# ProPrj_OpenCartGBA_2024-06-17.net
KiCad netlist of a schematic drawn in EasyEDA Pro
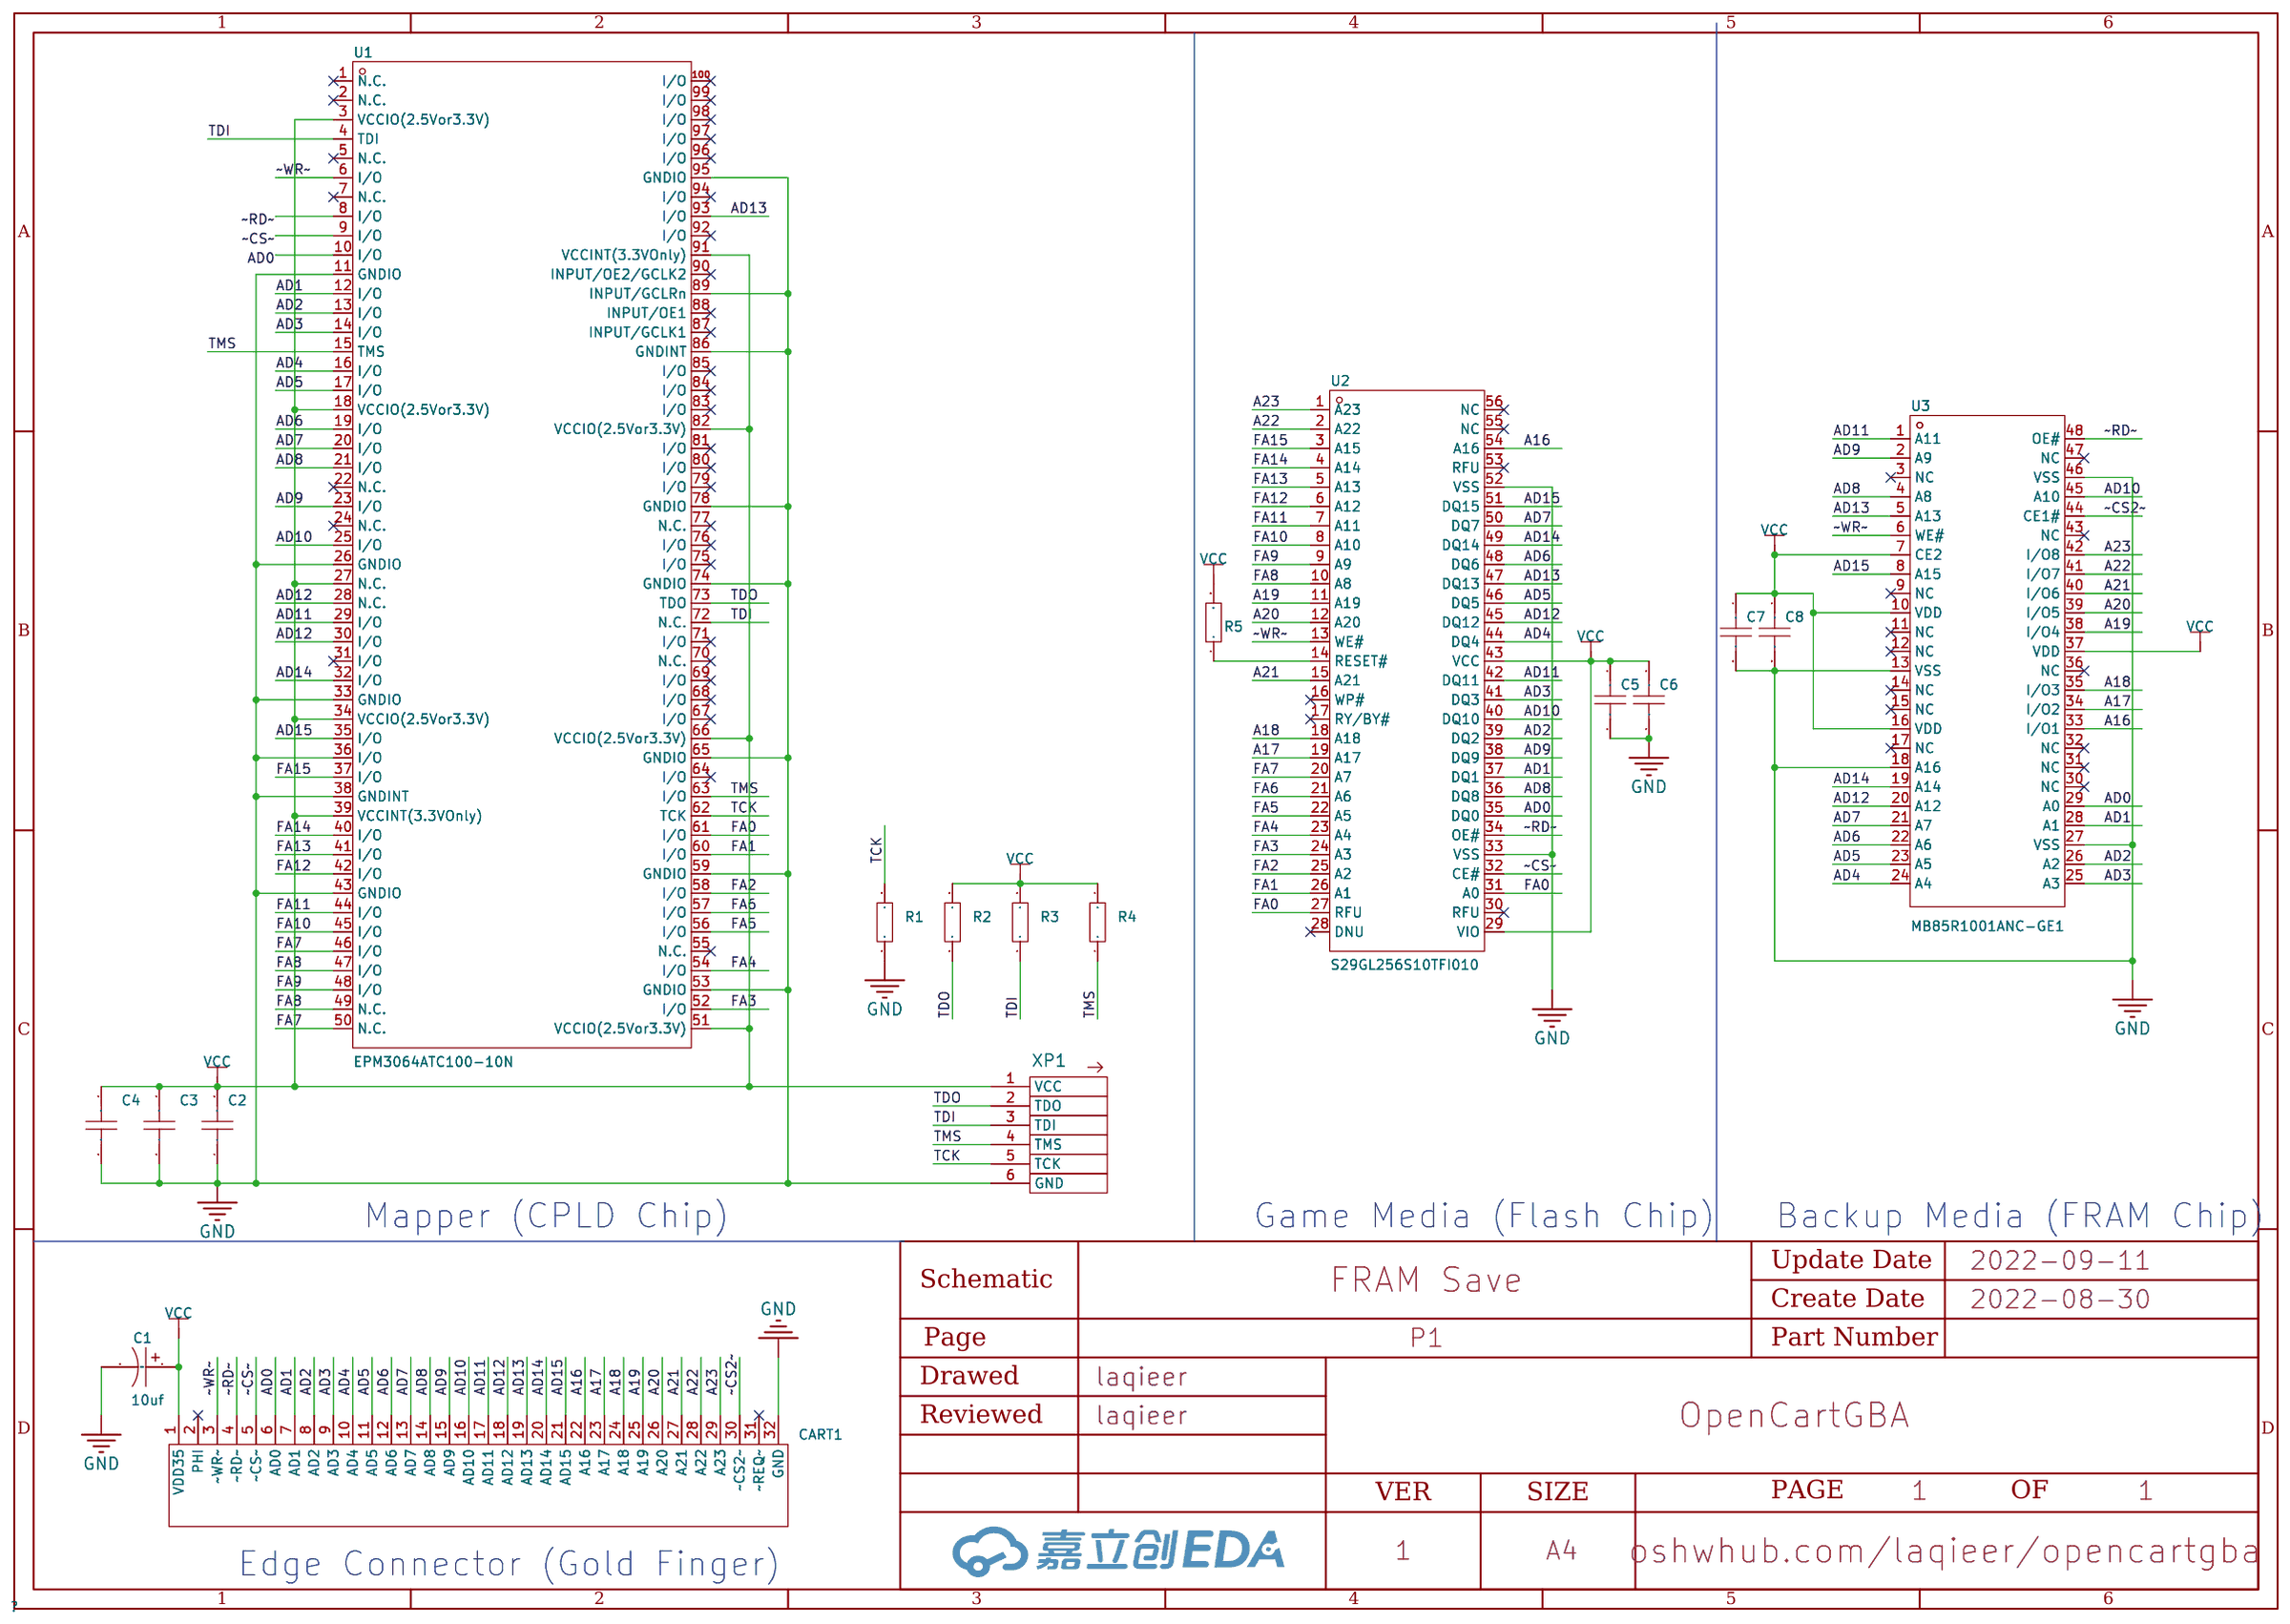
[diagram p0: schematic sheet]

(export (version "E")
  (design (tool "Eeschema 10.0.6"))
  (components
    (comp (ref "C1")
      (value "10uf")
      (footprint "easyedapro:CAP-SMD_L2.0-W1.3-FD")
      (libsource (lib "easyedapro") (part "10UF_C9900016685"))
    )
    (comp (ref "C2")
      (value "100nF/0603/50V")
      (footprint "easyedapro:C0603")
      (libsource (lib "easyedapro") (part "100NF/0603/50V"))
    )
    (comp (ref "C3")
      (value "100nF/0603/50V")
      (footprint "easyedapro:C0603")
      (libsource (lib "easyedapro") (part "100NF/0603/50V"))
    )
    (comp (ref "C4")
      (value "100nF/0603/50V")
      (footprint "easyedapro:C0603")
      (libsource (lib "easyedapro") (part "100NF/0603/50V"))
    )
    (comp (ref "C5")
      (value "100nF/0603/50V")
      (footprint "easyedapro:C0603")
      (libsource (lib "easyedapro") (part "100NF/0603/50V"))
    )
    (comp (ref "C6")
      (value "100nF/0603/50V")
      (footprint "easyedapro:C0603")
      (libsource (lib "easyedapro") (part "100NF/0603/50V"))
    )
    (comp (ref "C7")
      (value "100nF/0603/50V")
      (footprint "easyedapro:C0603")
      (libsource (lib "easyedapro") (part "100NF/0603/50V"))
    )
    (comp (ref "C8")
      (value "100nF/0603/50V")
      (footprint "easyedapro:C0603")
      (libsource (lib "easyedapro") (part "100NF/0603/50V"))
    )
    (comp (ref "CART1")
      (value "~")
      (footprint "easyedapro:GBACartridge")
      (description "GBA Cartridge")
      (libsource (lib "easyedapro") (part "GBACartridge"))
    )
    (comp (ref "R1")
      (value "10kΩ")
      (footprint "easyedapro:R0603")
      (description "电阻类型:薄膜电阻;阻值:10kΩ;精度:±0.1%;功率:100mW;温度系数:±25ppm/;最大工作电压:75V;工作温度范围:-55~+155;")
      (fields
        (field (name "Manufacturer Part") "TR0603B10K0P0525Z")
        (field (name "Manufacturer") "EVER OHMS(天二科技)")
      )
      (libsource (lib "easyedapro") (part "TR0603B10KP05250.1W"))
    )
    (comp (ref "R2")
      (value "10kΩ")
      (footprint "easyedapro:R0603")
      (description "电阻类型:薄膜电阻;阻值:10kΩ;精度:±0.1%;功率:100mW;温度系数:±25ppm/;最大工作电压:75V;工作温度范围:-55~+155;")
      (fields
        (field (name "Manufacturer Part") "TR0603B10K0P0525Z")
        (field (name "Manufacturer") "EVER OHMS(天二科技)")
      )
      (libsource (lib "easyedapro") (part "TR0603B10KP05250.1W"))
    )
    (comp (ref "R3")
      (value "10kΩ")
      (footprint "easyedapro:R0603")
      (description "电阻类型:薄膜电阻;阻值:10kΩ;精度:±0.1%;功率:100mW;温度系数:±25ppm/;最大工作电压:75V;工作温度范围:-55~+155;")
      (fields
        (field (name "Manufacturer Part") "TR0603B10K0P0525Z")
        (field (name "Manufacturer") "EVER OHMS(天二科技)")
      )
      (libsource (lib "easyedapro") (part "TR0603B10KP05250.1W"))
    )
    (comp (ref "R4")
      (value "10kΩ")
      (footprint "easyedapro:R0603")
      (description "电阻类型:薄膜电阻;阻值:10kΩ;精度:±0.1%;功率:100mW;温度系数:±25ppm/;最大工作电压:75V;工作温度范围:-55~+155;")
      (fields
        (field (name "Manufacturer Part") "TR0603B10K0P0525Z")
        (field (name "Manufacturer") "EVER OHMS(天二科技)")
      )
      (libsource (lib "easyedapro") (part "TR0603B10KP05250.1W"))
    )
    (comp (ref "R5")
      (value "10kΩ")
      (footprint "easyedapro:R0603")
      (description "电阻类型:薄膜电阻;阻值:10kΩ;精度:±0.1%;功率:100mW;温度系数:±25ppm/;最大工作电压:75V;工作温度范围:-55~+155;")
      (fields
        (field (name "Manufacturer Part") "TR0603B10K0P0525Z")
        (field (name "Manufacturer") "EVER OHMS(天二科技)")
      )
      (libsource (lib "easyedapro") (part "TR0603B10KP05250.1W"))
    )
    (comp (ref "U1")
      (value "EPM3064ATC100-10N")
      (footprint "easyedapro:TQFP-100_L14.0-W14.0-P0.50-LS16.0-BL")
      (description "可编程类型:-;逻辑元件/块数:-;宏单元数:-;I/O 数:-;工作温度:-;")
      (fields (field (name "Manufacturer") "Intel/Altera"))
      (libsource (lib "easyedapro") (part "EPM3064ATC100-10N"))
    )
    (comp (ref "U2")
      (value "S29GL256S10TFI010")
      (footprint "easyedapro:TSOP-56_L18.4-W14.0-P0.50-LS20.0-TL")
      (fields (field (name "Manufacturer") "SPANSION(飞索)"))
      (libsource (lib "easyedapro") (part "S29GL256S10TFI010"))
    )
    (comp (ref "U3")
      (value "MB85R1001ANC-GE1")
      (footprint "easyedapro:TSOP-48_L12.4-W12.2-P0.50-LS14.0-BL")
      (description "存储器容量:1Mb (128K x 8);存储器接口类型:Parallel;工作电压:3V ~ 3.6V;")
      (fields (field (name "Manufacturer") "FUJITSU(富士通)"))
      (libsource (lib "easyedapro") (part "MB85R1001ANC-GE1"))
    )
    (comp (ref "XP1")
      (value "JTAG")
      (footprint "easyedapro:JTAG_5P-P2.54")
      (libsource (lib "easyedapro") (part "jtag"))
    )
  )
  (nets
    (net (code "1") (name "/A16") (class "Default")
      (node (ref "CART1") (pin "22") (pinfunction "A16_22") (pintype "input"))
      (node (ref "U2") (pin "54") (pinfunction "A16_54") (pintype "input"))
      (node (ref "U3") (pin "33") (pinfunction "I/O1_33") (pintype "input"))
    )
    (net (code "2") (name "/A17") (class "Default")
      (node (ref "CART1") (pin "23") (pinfunction "A17_23") (pintype "input"))
      (node (ref "U2") (pin "19") (pinfunction "A17_19") (pintype "input"))
      (node (ref "U3") (pin "34") (pinfunction "I/O2_34") (pintype "input"))
    )
    (net (code "3") (name "/A18") (class "Default")
      (node (ref "CART1") (pin "24") (pinfunction "A18_24") (pintype "input"))
      (node (ref "U2") (pin "18") (pinfunction "A18_18") (pintype "input"))
      (node (ref "U3") (pin "35") (pinfunction "I/O3_35") (pintype "input"))
    )
    (net (code "4") (name "/A19") (class "Default")
      (node (ref "CART1") (pin "25") (pinfunction "A19_25") (pintype "input"))
      (node (ref "U2") (pin "11") (pinfunction "A19_11") (pintype "input"))
      (node (ref "U3") (pin "38") (pinfunction "I/O4_38") (pintype "input"))
    )
    (net (code "5") (name "/A20") (class "Default")
      (node (ref "CART1") (pin "26") (pinfunction "A20_26") (pintype "input"))
      (node (ref "U2") (pin "12") (pinfunction "A20_12") (pintype "input"))
      (node (ref "U3") (pin "39") (pinfunction "I/O5_39") (pintype "input"))
    )
    (net (code "6") (name "/A21") (class "Default")
      (node (ref "CART1") (pin "27") (pinfunction "A21_27") (pintype "input"))
      (node (ref "U2") (pin "15") (pinfunction "A21_15") (pintype "input"))
      (node (ref "U3") (pin "40") (pinfunction "I/O6_40") (pintype "input"))
    )
    (net (code "7") (name "/A22") (class "Default")
      (node (ref "CART1") (pin "28") (pinfunction "A22_28") (pintype "input"))
      (node (ref "U2") (pin "2") (pinfunction "A22_2") (pintype "input"))
      (node (ref "U3") (pin "41") (pinfunction "I/O7_41") (pintype "input"))
    )
    (net (code "8") (name "/A23") (class "Default")
      (node (ref "CART1") (pin "29") (pinfunction "A23_29") (pintype "input"))
      (node (ref "U2") (pin "1") (pinfunction "A23_1") (pintype "input"))
      (node (ref "U3") (pin "42") (pinfunction "I/O8_42") (pintype "input"))
    )
    (net (code "9") (name "/AD0") (class "Default")
      (node (ref "CART1") (pin "6") (pinfunction "AD0_6") (pintype "input"))
      (node (ref "U1") (pin "10") (pinfunction "I/O_10") (pintype "input"))
      (node (ref "U2") (pin "35") (pinfunction "DQ0_35") (pintype "input"))
      (node (ref "U3") (pin "29") (pinfunction "A0_29") (pintype "input"))
    )
    (net (code "10") (name "/AD1") (class "Default")
      (node (ref "CART1") (pin "7") (pinfunction "AD1_7") (pintype "input"))
      (node (ref "U1") (pin "12") (pinfunction "I/O_12") (pintype "input"))
      (node (ref "U2") (pin "37") (pinfunction "DQ1_37") (pintype "input"))
      (node (ref "U3") (pin "28") (pinfunction "A1_28") (pintype "input"))
    )
    (net (code "11") (name "/AD2") (class "Default")
      (node (ref "CART1") (pin "8") (pinfunction "AD2_8") (pintype "input"))
      (node (ref "U1") (pin "13") (pinfunction "I/O_13") (pintype "input"))
      (node (ref "U2") (pin "39") (pinfunction "DQ2_39") (pintype "input"))
      (node (ref "U3") (pin "26") (pinfunction "A2_26") (pintype "input"))
    )
    (net (code "12") (name "/AD3") (class "Default")
      (node (ref "CART1") (pin "9") (pinfunction "AD3_9") (pintype "input"))
      (node (ref "U1") (pin "14") (pinfunction "I/O_14") (pintype "input"))
      (node (ref "U2") (pin "41") (pinfunction "DQ3_41") (pintype "input"))
      (node (ref "U3") (pin "25") (pinfunction "A3_25") (pintype "input"))
    )
    (net (code "13") (name "/AD4") (class "Default")
      (node (ref "CART1") (pin "10") (pinfunction "AD4_10") (pintype "input"))
      (node (ref "U1") (pin "16") (pinfunction "I/O_16") (pintype "input"))
      (node (ref "U2") (pin "44") (pinfunction "DQ4_44") (pintype "input"))
      (node (ref "U3") (pin "24") (pinfunction "A4_24") (pintype "input"))
    )
    (net (code "14") (name "/AD5") (class "Default")
      (node (ref "CART1") (pin "11") (pinfunction "AD5_11") (pintype "input"))
      (node (ref "U1") (pin "17") (pinfunction "I/O_17") (pintype "input"))
      (node (ref "U2") (pin "46") (pinfunction "DQ5_46") (pintype "input"))
      (node (ref "U3") (pin "23") (pinfunction "A5_23") (pintype "input"))
    )
    (net (code "15") (name "/AD6") (class "Default")
      (node (ref "CART1") (pin "12") (pinfunction "AD6_12") (pintype "input"))
      (node (ref "U1") (pin "19") (pinfunction "I/O_19") (pintype "input"))
      (node (ref "U2") (pin "48") (pinfunction "DQ6_48") (pintype "input"))
      (node (ref "U3") (pin "22") (pinfunction "A6_22") (pintype "input"))
    )
    (net (code "16") (name "/AD7") (class "Default")
      (node (ref "CART1") (pin "13") (pinfunction "AD7_13") (pintype "input"))
      (node (ref "U1") (pin "20") (pinfunction "I/O_20") (pintype "input"))
      (node (ref "U2") (pin "50") (pinfunction "DQ7_50") (pintype "input"))
      (node (ref "U3") (pin "21") (pinfunction "A7_21") (pintype "input"))
    )
    (net (code "17") (name "/AD8") (class "Default")
      (node (ref "CART1") (pin "14") (pinfunction "AD8_14") (pintype "input"))
      (node (ref "U1") (pin "21") (pinfunction "I/O_21") (pintype "input"))
      (node (ref "U2") (pin "36") (pinfunction "DQ8_36") (pintype "input"))
      (node (ref "U3") (pin "4") (pinfunction "A8_4") (pintype "input"))
    )
    (net (code "18") (name "/AD9") (class "Default")
      (node (ref "CART1") (pin "15") (pinfunction "AD9_15") (pintype "input"))
      (node (ref "U1") (pin "23") (pinfunction "I/O_23") (pintype "input"))
      (node (ref "U2") (pin "38") (pinfunction "DQ9_38") (pintype "input"))
      (node (ref "U3") (pin "2") (pinfunction "A9_2") (pintype "input"))
    )
    (net (code "19") (name "/AD10") (class "Default")
      (node (ref "CART1") (pin "16") (pinfunction "AD10_16") (pintype "input"))
      (node (ref "U1") (pin "25") (pinfunction "I/O_25") (pintype "input"))
      (node (ref "U2") (pin "40") (pinfunction "DQ10_40") (pintype "input"))
      (node (ref "U3") (pin "45") (pinfunction "A10_45") (pintype "input"))
    )
    (net (code "20") (name "/AD11") (class "Default")
      (node (ref "CART1") (pin "17") (pinfunction "AD11_17") (pintype "input"))
      (node (ref "U1") (pin "29") (pinfunction "I/O_29") (pintype "input"))
      (node (ref "U2") (pin "42") (pinfunction "DQ11_42") (pintype "input"))
      (node (ref "U3") (pin "1") (pinfunction "A11_1") (pintype "input"))
    )
    (net (code "21") (name "/AD12") (class "Default")
      (node (ref "CART1") (pin "18") (pinfunction "AD12_18") (pintype "input"))
      (node (ref "U1") (pin "28") (pinfunction "N.C._28") (pintype "input"))
      (node (ref "U1") (pin "30") (pinfunction "I/O_30") (pintype "input"))
      (node (ref "U2") (pin "45") (pinfunction "DQ12_45") (pintype "input"))
      (node (ref "U3") (pin "20") (pinfunction "A12_20") (pintype "input"))
    )
    (net (code "22") (name "/AD13") (class "Default")
      (node (ref "CART1") (pin "19") (pinfunction "AD13_19") (pintype "input"))
      (node (ref "U1") (pin "93") (pinfunction "I/O_93") (pintype "input"))
      (node (ref "U2") (pin "47") (pinfunction "DQ13_47") (pintype "input"))
      (node (ref "U3") (pin "5") (pinfunction "A13_5") (pintype "input"))
    )
    (net (code "23") (name "/AD14") (class "Default")
      (node (ref "CART1") (pin "20") (pinfunction "AD14_20") (pintype "input"))
      (node (ref "U1") (pin "32") (pinfunction "I/O_32") (pintype "input"))
      (node (ref "U2") (pin "49") (pinfunction "DQ14_49") (pintype "input"))
      (node (ref "U3") (pin "19") (pinfunction "A14_19") (pintype "input"))
    )
    (net (code "24") (name "/AD15") (class "Default")
      (node (ref "CART1") (pin "21") (pinfunction "AD15_21") (pintype "input"))
      (node (ref "U1") (pin "35") (pinfunction "I/O_35") (pintype "input"))
      (node (ref "U2") (pin "51") (pinfunction "DQ15_51") (pintype "input"))
      (node (ref "U3") (pin "8") (pinfunction "A15_8") (pintype "input"))
    )
    (net (code "25") (name "/FA0") (class "Default")
      (node (ref "U1") (pin "61") (pinfunction "I/O_61") (pintype "input"))
      (node (ref "U2") (pin "27") (pinfunction "RFU_27") (pintype "input"))
      (node (ref "U2") (pin "31") (pinfunction "A0_31") (pintype "input"))
    )
    (net (code "26") (name "/FA1") (class "Default")
      (node (ref "U1") (pin "60") (pinfunction "I/O_60") (pintype "input"))
      (node (ref "U2") (pin "26") (pinfunction "A1_26") (pintype "input"))
    )
    (net (code "27") (name "/FA2") (class "Default")
      (node (ref "U1") (pin "58") (pinfunction "I/O_58") (pintype "input"))
      (node (ref "U2") (pin "25") (pinfunction "A2_25") (pintype "input"))
    )
    (net (code "28") (name "/FA3") (class "Default")
      (node (ref "U1") (pin "52") (pinfunction "I/O_52") (pintype "input"))
      (node (ref "U2") (pin "24") (pinfunction "A3_24") (pintype "input"))
    )
    (net (code "29") (name "/FA4") (class "Default")
      (node (ref "U1") (pin "54") (pinfunction "I/O_54") (pintype "input"))
      (node (ref "U2") (pin "23") (pinfunction "A4_23") (pintype "input"))
    )
    (net (code "30") (name "/FA5") (class "Default")
      (node (ref "U1") (pin "56") (pinfunction "I/O_56") (pintype "input"))
      (node (ref "U2") (pin "22") (pinfunction "A5_22") (pintype "input"))
    )
    (net (code "31") (name "/FA6") (class "Default")
      (node (ref "U1") (pin "57") (pinfunction "I/O_57") (pintype "input"))
      (node (ref "U2") (pin "21") (pinfunction "A6_21") (pintype "input"))
    )
    (net (code "32") (name "/FA7") (class "Default")
      (node (ref "U1") (pin "46") (pinfunction "I/O_46") (pintype "input"))
      (node (ref "U1") (pin "50") (pinfunction "N.C._50") (pintype "input"))
      (node (ref "U2") (pin "20") (pinfunction "A7_20") (pintype "input"))
    )
    (net (code "33") (name "/FA8") (class "Default")
      (node (ref "U1") (pin "47") (pinfunction "I/O_47") (pintype "input"))
      (node (ref "U1") (pin "49") (pinfunction "N.C._49") (pintype "input"))
      (node (ref "U2") (pin "10") (pinfunction "A8_10") (pintype "input"))
    )
    (net (code "34") (name "/FA9") (class "Default")
      (node (ref "U1") (pin "48") (pinfunction "I/O_48") (pintype "input"))
      (node (ref "U2") (pin "9") (pinfunction "A9_9") (pintype "input"))
    )
    (net (code "35") (name "/FA10") (class "Default")
      (node (ref "U1") (pin "45") (pinfunction "I/O_45") (pintype "input"))
      (node (ref "U2") (pin "8") (pinfunction "A10_8") (pintype "input"))
    )
    (net (code "36") (name "/FA11") (class "Default")
      (node (ref "U1") (pin "44") (pinfunction "I/O_44") (pintype "input"))
      (node (ref "U2") (pin "7") (pinfunction "A11_7") (pintype "input"))
    )
    (net (code "37") (name "/FA12") (class "Default")
      (node (ref "U1") (pin "42") (pinfunction "I/O_42") (pintype "input"))
      (node (ref "U2") (pin "6") (pinfunction "A12_6") (pintype "input"))
    )
    (net (code "38") (name "/FA13") (class "Default")
      (node (ref "U1") (pin "41") (pinfunction "I/O_41") (pintype "input"))
      (node (ref "U2") (pin "5") (pinfunction "A13_5") (pintype "input"))
    )
    (net (code "39") (name "/FA14") (class "Default")
      (node (ref "U1") (pin "40") (pinfunction "I/O_40") (pintype "input"))
      (node (ref "U2") (pin "4") (pinfunction "A14_4") (pintype "input"))
    )
    (net (code "40") (name "/FA15") (class "Default")
      (node (ref "U1") (pin "37") (pinfunction "I/O_37") (pintype "input"))
      (node (ref "U2") (pin "3") (pinfunction "A15_3") (pintype "input"))
    )
    (net (code "41") (name "/TCK") (class "Default")
      (node (ref "R1") (pin "2") (pinfunction "2_2") (pintype "input"))
      (node (ref "U1") (pin "62") (pinfunction "TCK_62") (pintype "input"))
      (node (ref "XP1") (pin "5") (pinfunction "TCK_5") (pintype "input"))
    )
    (net (code "42") (name "/TDI") (class "Default")
      (node (ref "R3") (pin "1") (pinfunction "1_1") (pintype "input"))
      (node (ref "U1") (pin "4") (pinfunction "TDI_4") (pintype "input"))
      (node (ref "U1") (pin "72") (pinfunction "N.C._72") (pintype "input"))
      (node (ref "XP1") (pin "3") (pinfunction "TDI_3") (pintype "output"))
    )
    (net (code "43") (name "/TDO") (class "Default")
      (node (ref "R2") (pin "1") (pinfunction "1_1") (pintype "input"))
      (node (ref "U1") (pin "73") (pinfunction "TDO_73") (pintype "input"))
      (node (ref "XP1") (pin "2") (pinfunction "TDO_2") (pintype "output"))
    )
    (net (code "44") (name "/TMS") (class "Default")
      (node (ref "R4") (pin "1") (pinfunction "1_1") (pintype "input"))
      (node (ref "U1") (pin "15") (pinfunction "TMS_15") (pintype "input"))
      (node (ref "U1") (pin "63") (pinfunction "I/O_63") (pintype "input"))
      (node (ref "XP1") (pin "4") (pinfunction "TMS_4") (pintype "output"))
    )
    (net (code "45") (name "/~CS2~") (class "Default")
      (node (ref "CART1") (pin "30") (pinfunction "~CS2~_30") (pintype "input"))
      (node (ref "U3") (pin "44") (pinfunction "CE1#_44") (pintype "input"))
    )
    (net (code "46") (name "/~CS~") (class "Default")
      (node (ref "CART1") (pin "5") (pinfunction "~CS~_5") (pintype "input"))
      (node (ref "U1") (pin "9") (pinfunction "I/O_9") (pintype "input"))
      (node (ref "U2") (pin "32") (pinfunction "CE#_32") (pintype "input"))
    )
    (net (code "47") (name "/~RD~") (class "Default")
      (node (ref "CART1") (pin "4") (pinfunction "~RD~_4") (pintype "input"))
      (node (ref "U1") (pin "8") (pinfunction "I/O_8") (pintype "input"))
      (node (ref "U2") (pin "34") (pinfunction "OE#_34") (pintype "input"))
      (node (ref "U3") (pin "48") (pinfunction "OE#_48") (pintype "input"))
    )
    (net (code "48") (name "/~WR~") (class "Default")
      (node (ref "CART1") (pin "3") (pinfunction "~WR~_3") (pintype "input"))
      (node (ref "U1") (pin "6") (pinfunction "I/O_6") (pintype "input"))
      (node (ref "U2") (pin "13") (pinfunction "WE#_13") (pintype "input"))
      (node (ref "U3") (pin "6") (pinfunction "WE#_6") (pintype "input"))
    )
    (net (code "49") (name "GND") (class "Default")
      (node (ref "C1") (pin "2") (pinfunction "2_2") (pintype "input"))
      (node (ref "C2") (pin "1") (pinfunction "1_1") (pintype "input"))
      (node (ref "C3") (pin "2") (pinfunction "2_2") (pintype "input"))
      (node (ref "C4") (pin "2") (pinfunction "2_2") (pintype "input"))
      (node (ref "C5") (pin "2") (pinfunction "2_2") (pintype "input"))
      (node (ref "C6") (pin "2") (pinfunction "2_2") (pintype "input"))
      (node (ref "C7") (pin "2") (pinfunction "2_2") (pintype "input"))
      (node (ref "C8") (pin "2") (pinfunction "2_2") (pintype "input"))
      (node (ref "CART1") (pin "32") (pinfunction "GND_32") (pintype "input"))
      (node (ref "R1") (pin "1") (pinfunction "1_1") (pintype "input"))
      (node (ref "U1") (pin "11") (pinfunction "GNDIO_11") (pintype "input"))
      (node (ref "U1") (pin "26") (pinfunction "GNDIO_26") (pintype "input"))
      (node (ref "U1") (pin "33") (pinfunction "GNDIO_33") (pintype "input"))
      (node (ref "U1") (pin "36") (pinfunction "I/O_36") (pintype "input"))
      (node (ref "U1") (pin "38") (pinfunction "GNDINT_38") (pintype "input"))
      (node (ref "U1") (pin "43") (pinfunction "GNDIO_43") (pintype "input"))
      (node (ref "U1") (pin "53") (pinfunction "GNDIO_53") (pintype "input"))
      (node (ref "U1") (pin "59") (pinfunction "GNDIO_59") (pintype "input"))
      (node (ref "U1") (pin "65") (pinfunction "GNDIO_65") (pintype "input"))
      (node (ref "U1") (pin "74") (pinfunction "GNDIO_74") (pintype "input"))
      (node (ref "U1") (pin "78") (pinfunction "GNDIO_78") (pintype "input"))
      (node (ref "U1") (pin "86") (pinfunction "GNDINT_86") (pintype "input"))
      (node (ref "U1") (pin "89") (pinfunction "INPUT/GCLRn_89") (pintype "input"))
      (node (ref "U1") (pin "95") (pinfunction "GNDIO_95") (pintype "input"))
      (node (ref "U2") (pin "33") (pinfunction "VSS_33") (pintype "input"))
      (node (ref "U2") (pin "52") (pinfunction "VSS_52") (pintype "input"))
      (node (ref "U3") (pin "13") (pinfunction "VSS_13") (pintype "input"))
      (node (ref "U3") (pin "18") (pinfunction "A16_18") (pintype "input"))
      (node (ref "U3") (pin "27") (pinfunction "VSS_27") (pintype "input"))
      (node (ref "U3") (pin "46") (pinfunction "VSS_46") (pintype "input"))
      (node (ref "XP1") (pin "6") (pinfunction "GND_6") (pintype "input"))
    )
    (net (code "50") (name "Net-(U2-RESET#)") (class "Default")
      (node (ref "R5") (pin "1") (pinfunction "1_1") (pintype "input"))
      (node (ref "U2") (pin "14") (pinfunction "RESET#_14") (pintype "input"))
    )
    (net (code "51") (name "VCC") (class "Default")
      (node (ref "C1") (pin "1") (pinfunction "1_1") (pintype "input"))
      (node (ref "C2") (pin "2") (pinfunction "2_2") (pintype "input"))
      (node (ref "C3") (pin "1") (pinfunction "1_1") (pintype "input"))
      (node (ref "C4") (pin "1") (pinfunction "1_1") (pintype "input"))
      (node (ref "C5") (pin "1") (pinfunction "1_1") (pintype "input"))
      (node (ref "C6") (pin "1") (pinfunction "1_1") (pintype "input"))
      (node (ref "C7") (pin "1") (pinfunction "1_1") (pintype "input"))
      (node (ref "C8") (pin "1") (pinfunction "1_1") (pintype "input"))
      (node (ref "CART1") (pin "1") (pinfunction "VDD35_1") (pintype "input"))
      (node (ref "R2") (pin "2") (pinfunction "2_2") (pintype "input"))
      (node (ref "R3") (pin "2") (pinfunction "2_2") (pintype "input"))
      (node (ref "R4") (pin "2") (pinfunction "2_2") (pintype "input"))
      (node (ref "R5") (pin "2") (pinfunction "2_2") (pintype "input"))
      (node (ref "U1") (pin "18") (pinfunction "VCCIO(2.5Vor3.3V)_18") (pintype "input"))
      (node (ref "U1") (pin "27") (pinfunction "N.C._27") (pintype "input"))
      (node (ref "U1") (pin "3") (pinfunction "VCCIO(2.5Vor3.3V)_3") (pintype "input"))
      (node (ref "U1") (pin "34") (pinfunction "VCCIO(2.5Vor3.3V)_34") (pintype "input"))
      (node (ref "U1") (pin "39") (pinfunction "VCCINT(3.3VOnly)_39") (pintype "input"))
      (node (ref "U1") (pin "51") (pinfunction "VCCIO(2.5Vor3.3V)_51") (pintype "input"))
      (node (ref "U1") (pin "66") (pinfunction "VCCIO(2.5Vor3.3V)_66") (pintype "input"))
      (node (ref "U1") (pin "82") (pinfunction "VCCIO(2.5Vor3.3V)_82") (pintype "input"))
      (node (ref "U1") (pin "91") (pinfunction "VCCINT(3.3VOnly)_91") (pintype "input"))
      (node (ref "U2") (pin "29") (pinfunction "VIO_29") (pintype "input"))
      (node (ref "U2") (pin "43") (pinfunction "VCC_43") (pintype "input"))
      (node (ref "U3") (pin "10") (pinfunction "VDD_10") (pintype "input"))
      (node (ref "U3") (pin "16") (pinfunction "VDD_16") (pintype "input"))
      (node (ref "U3") (pin "37") (pinfunction "VDD_37") (pintype "input"))
      (node (ref "U3") (pin "7") (pinfunction "CE2_7") (pintype "input"))
      (node (ref "XP1") (pin "1") (pinfunction "VCC_1") (pintype "output"))
    )
    (net (code "52") (name "unconnected-(CART1-PHI-Pad2)") (class "Default")
      (node (ref "CART1") (pin "2") (pinfunction "PHI_2") (pintype "input+no_connect"))
    )
    (net (code "53") (name "unconnected-(CART1-~REQ~-Pad31)") (class "Default")
      (node (ref "CART1") (pin "31") (pinfunction "~REQ~_31") (pintype "input+no_connect"))
    )
    (net (code "54") (name "unconnected-(U1-INPUT{slash}GCLK1-Pad87)") (class "Default")
      (node (ref "U1") (pin "87") (pinfunction "INPUT/GCLK1_87") (pintype "input+no_connect"))
    )
    (net (code "55") (name "unconnected-(U1-INPUT{slash}OE1-Pad88)") (class "Default")
      (node (ref "U1") (pin "88") (pinfunction "INPUT/OE1_88") (pintype "input+no_connect"))
    )
    (net (code "56") (name "unconnected-(U1-INPUT{slash}OE2{slash}GCLK2-Pad90)") (class "Default")
      (node (ref "U1") (pin "90") (pinfunction "INPUT/OE2/GCLK2_90") (pintype "input+no_connect"))
    )
    (net (code "57") (name "unconnected-(U1-I{slash}O-Pad31)") (class "Default")
      (node (ref "U1") (pin "31") (pinfunction "I/O_31") (pintype "input+no_connect"))
    )
    (net (code "58") (name "unconnected-(U1-I{slash}O-Pad64)") (class "Default")
      (node (ref "U1") (pin "64") (pinfunction "I/O_64") (pintype "input+no_connect"))
    )
    (net (code "59") (name "unconnected-(U1-I{slash}O-Pad67)") (class "Default")
      (node (ref "U1") (pin "67") (pinfunction "I/O_67") (pintype "input+no_connect"))
    )
    (net (code "60") (name "unconnected-(U1-I{slash}O-Pad68)") (class "Default")
      (node (ref "U1") (pin "68") (pinfunction "I/O_68") (pintype "input+no_connect"))
    )
    (net (code "61") (name "unconnected-(U1-I{slash}O-Pad69)") (class "Default")
      (node (ref "U1") (pin "69") (pinfunction "I/O_69") (pintype "input+no_connect"))
    )
    (net (code "62") (name "unconnected-(U1-I{slash}O-Pad71)") (class "Default")
      (node (ref "U1") (pin "71") (pinfunction "I/O_71") (pintype "input+no_connect"))
    )
    (net (code "63") (name "unconnected-(U1-I{slash}O-Pad75)") (class "Default")
      (node (ref "U1") (pin "75") (pinfunction "I/O_75") (pintype "input+no_connect"))
    )
    (net (code "64") (name "unconnected-(U1-I{slash}O-Pad76)") (class "Default")
      (node (ref "U1") (pin "76") (pinfunction "I/O_76") (pintype "input+no_connect"))
    )
    (net (code "65") (name "unconnected-(U1-I{slash}O-Pad79)") (class "Default")
      (node (ref "U1") (pin "79") (pinfunction "I/O_79") (pintype "input+no_connect"))
    )
    (net (code "66") (name "unconnected-(U1-I{slash}O-Pad80)") (class "Default")
      (node (ref "U1") (pin "80") (pinfunction "I/O_80") (pintype "input+no_connect"))
    )
    (net (code "67") (name "unconnected-(U1-I{slash}O-Pad81)") (class "Default")
      (node (ref "U1") (pin "81") (pinfunction "I/O_81") (pintype "input+no_connect"))
    )
    (net (code "68") (name "unconnected-(U1-I{slash}O-Pad83)") (class "Default")
      (node (ref "U1") (pin "83") (pinfunction "I/O_83") (pintype "input+no_connect"))
    )
    (net (code "69") (name "unconnected-(U1-I{slash}O-Pad84)") (class "Default")
      (node (ref "U1") (pin "84") (pinfunction "I/O_84") (pintype "input+no_connect"))
    )
    (net (code "70") (name "unconnected-(U1-I{slash}O-Pad85)") (class "Default")
      (node (ref "U1") (pin "85") (pinfunction "I/O_85") (pintype "input+no_connect"))
    )
    (net (code "71") (name "unconnected-(U1-I{slash}O-Pad92)") (class "Default")
      (node (ref "U1") (pin "92") (pinfunction "I/O_92") (pintype "input+no_connect"))
    )
    (net (code "72") (name "unconnected-(U1-I{slash}O-Pad94)") (class "Default")
      (node (ref "U1") (pin "94") (pinfunction "I/O_94") (pintype "input+no_connect"))
    )
    (net (code "73") (name "unconnected-(U1-I{slash}O-Pad96)") (class "Default")
      (node (ref "U1") (pin "96") (pinfunction "I/O_96") (pintype "input+no_connect"))
    )
    (net (code "74") (name "unconnected-(U1-I{slash}O-Pad97)") (class "Default")
      (node (ref "U1") (pin "97") (pinfunction "I/O_97") (pintype "input+no_connect"))
    )
    (net (code "75") (name "unconnected-(U1-I{slash}O-Pad98)") (class "Default")
      (node (ref "U1") (pin "98") (pinfunction "I/O_98") (pintype "input+no_connect"))
    )
    (net (code "76") (name "unconnected-(U1-I{slash}O-Pad99)") (class "Default")
      (node (ref "U1") (pin "99") (pinfunction "I/O_99") (pintype "input+no_connect"))
    )
    (net (code "77") (name "unconnected-(U1-I{slash}O-Pad100)") (class "Default")
      (node (ref "U1") (pin "100") (pinfunction "I/O_100") (pintype "input+no_connect"))
    )
    (net (code "78") (name "unconnected-(U1-N.C.-Pad1)") (class "Default")
      (node (ref "U1") (pin "1") (pinfunction "N.C._1") (pintype "input+no_connect"))
    )
    (net (code "79") (name "unconnected-(U1-N.C.-Pad2)") (class "Default")
      (node (ref "U1") (pin "2") (pinfunction "N.C._2") (pintype "input+no_connect"))
    )
    (net (code "80") (name "unconnected-(U1-N.C.-Pad5)") (class "Default")
      (node (ref "U1") (pin "5") (pinfunction "N.C._5") (pintype "input+no_connect"))
    )
    (net (code "81") (name "unconnected-(U1-N.C.-Pad7)") (class "Default")
      (node (ref "U1") (pin "7") (pinfunction "N.C._7") (pintype "input+no_connect"))
    )
    (net (code "82") (name "unconnected-(U1-N.C.-Pad22)") (class "Default")
      (node (ref "U1") (pin "22") (pinfunction "N.C._22") (pintype "input+no_connect"))
    )
    (net (code "83") (name "unconnected-(U1-N.C.-Pad24)") (class "Default")
      (node (ref "U1") (pin "24") (pinfunction "N.C._24") (pintype "input+no_connect"))
    )
    (net (code "84") (name "unconnected-(U1-N.C.-Pad55)") (class "Default")
      (node (ref "U1") (pin "55") (pinfunction "N.C._55") (pintype "input+no_connect"))
    )
    (net (code "85") (name "unconnected-(U1-N.C.-Pad70)") (class "Default")
      (node (ref "U1") (pin "70") (pinfunction "N.C._70") (pintype "input+no_connect"))
    )
    (net (code "86") (name "unconnected-(U1-N.C.-Pad77)") (class "Default")
      (node (ref "U1") (pin "77") (pinfunction "N.C._77") (pintype "input+no_connect"))
    )
    (net (code "87") (name "unconnected-(U2-DNU-Pad28)") (class "Default")
      (node (ref "U2") (pin "28") (pinfunction "DNU_28") (pintype "input+no_connect"))
    )
    (net (code "88") (name "unconnected-(U2-NC-Pad55)") (class "Default")
      (node (ref "U2") (pin "55") (pinfunction "NC_55") (pintype "input+no_connect"))
    )
    (net (code "89") (name "unconnected-(U2-NC-Pad56)") (class "Default")
      (node (ref "U2") (pin "56") (pinfunction "NC_56") (pintype "input+no_connect"))
    )
    (net (code "90") (name "unconnected-(U2-RFU-Pad30)") (class "Default")
      (node (ref "U2") (pin "30") (pinfunction "RFU_30") (pintype "input+no_connect"))
    )
    (net (code "91") (name "unconnected-(U2-RFU-Pad53)") (class "Default")
      (node (ref "U2") (pin "53") (pinfunction "RFU_53") (pintype "input+no_connect"))
    )
    (net (code "92") (name "unconnected-(U2-RY{slash}BY#-Pad17)") (class "Default")
      (node (ref "U2") (pin "17") (pinfunction "RY/BY#_17") (pintype "input+no_connect"))
    )
    (net (code "93") (name "unconnected-(U2-WP#-Pad16)") (class "Default")
      (node (ref "U2") (pin "16") (pinfunction "WP#_16") (pintype "input+no_connect"))
    )
    (net (code "94") (name "unconnected-(U3-NC-Pad3)") (class "Default")
      (node (ref "U3") (pin "3") (pinfunction "NC_3") (pintype "input+no_connect"))
    )
    (net (code "95") (name "unconnected-(U3-NC-Pad9)") (class "Default")
      (node (ref "U3") (pin "9") (pinfunction "NC_9") (pintype "input+no_connect"))
    )
    (net (code "96") (name "unconnected-(U3-NC-Pad11)") (class "Default")
      (node (ref "U3") (pin "11") (pinfunction "NC_11") (pintype "input+no_connect"))
    )
    (net (code "97") (name "unconnected-(U3-NC-Pad12)") (class "Default")
      (node (ref "U3") (pin "12") (pinfunction "NC_12") (pintype "input+no_connect"))
    )
    (net (code "98") (name "unconnected-(U3-NC-Pad14)") (class "Default")
      (node (ref "U3") (pin "14") (pinfunction "NC_14") (pintype "input+no_connect"))
    )
    (net (code "99") (name "unconnected-(U3-NC-Pad15)") (class "Default")
      (node (ref "U3") (pin "15") (pinfunction "NC_15") (pintype "input+no_connect"))
    )
    (net (code "100") (name "unconnected-(U3-NC-Pad17)") (class "Default")
      (node (ref "U3") (pin "17") (pinfunction "NC_17") (pintype "input+no_connect"))
    )
    (net (code "101") (name "unconnected-(U3-NC-Pad30)") (class "Default")
      (node (ref "U3") (pin "30") (pinfunction "NC_30") (pintype "input+no_connect"))
    )
    (net (code "102") (name "unconnected-(U3-NC-Pad31)") (class "Default")
      (node (ref "U3") (pin "31") (pinfunction "NC_31") (pintype "input+no_connect"))
    )
    (net (code "103") (name "unconnected-(U3-NC-Pad32)") (class "Default")
      (node (ref "U3") (pin "32") (pinfunction "NC_32") (pintype "input+no_connect"))
    )
    (net (code "104") (name "unconnected-(U3-NC-Pad36)") (class "Default")
      (node (ref "U3") (pin "36") (pinfunction "NC_36") (pintype "input+no_connect"))
    )
    (net (code "105") (name "unconnected-(U3-NC-Pad43)") (class "Default")
      (node (ref "U3") (pin "43") (pinfunction "NC_43") (pintype "input+no_connect"))
    )
    (net (code "106") (name "unconnected-(U3-NC-Pad47)") (class "Default")
      (node (ref "U3") (pin "47") (pinfunction "NC_47") (pintype "input+no_connect"))
    )
  )
)
